# MatrixLantern.net
KiCad netlist of a schematic drawn in Altium Designer
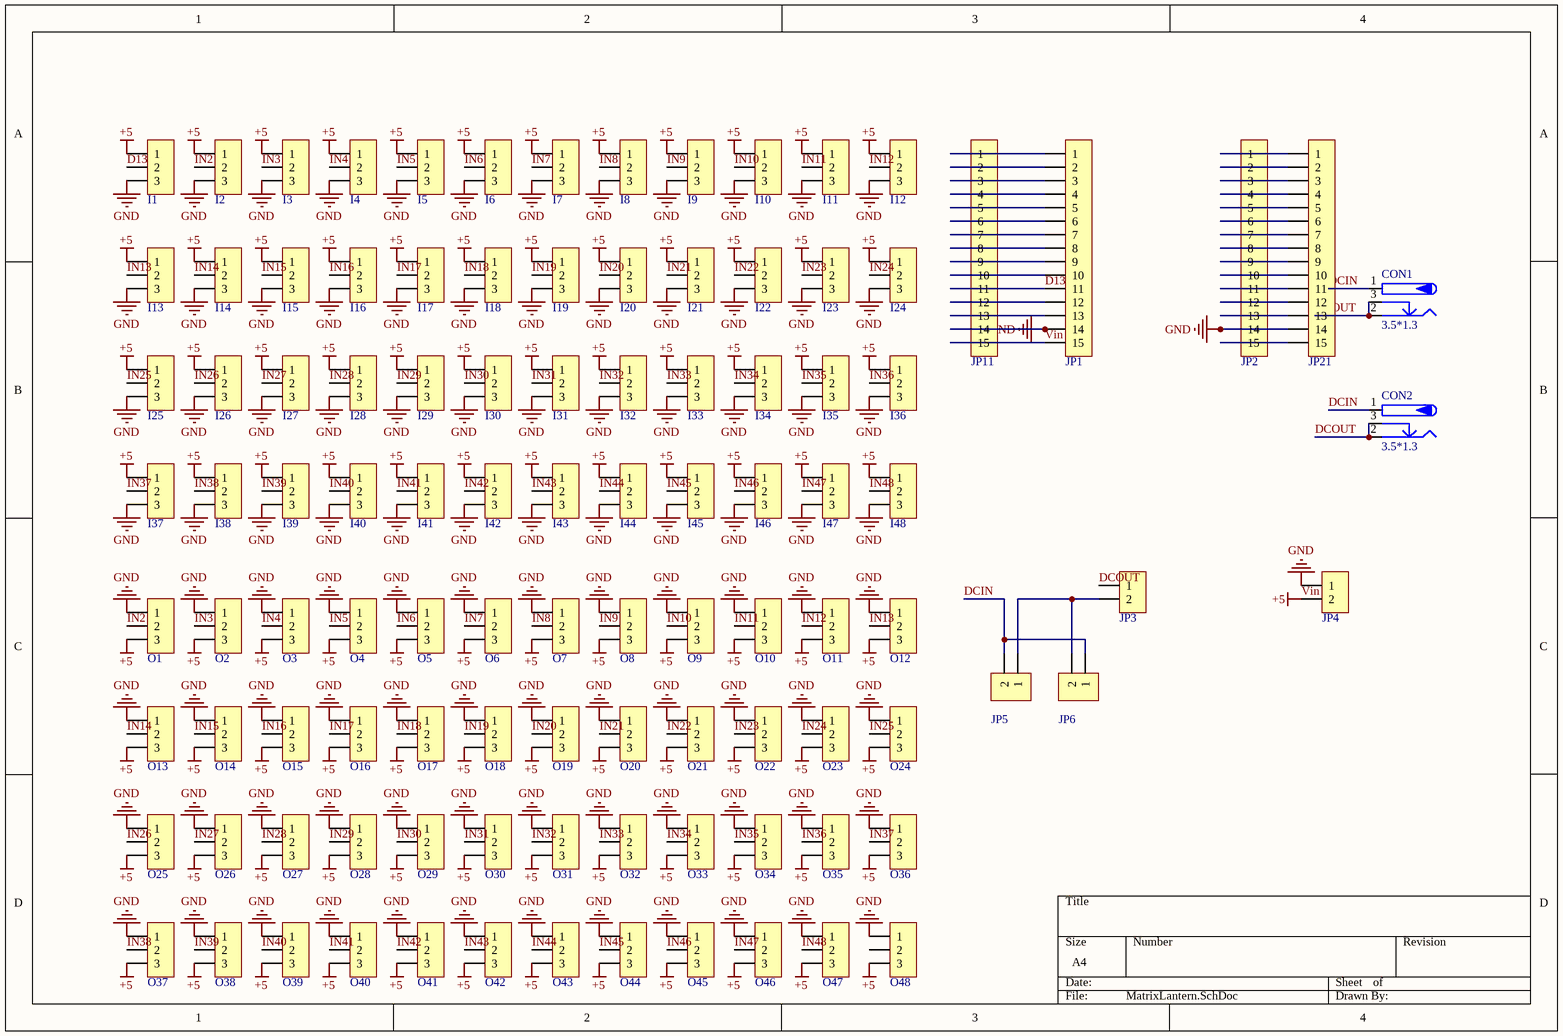
[diagram p0: MatrixLantern.SchDoc]

(export (version "E")
  (design (tool "Eeschema 10.0.6"))
  (components
    (comp (ref "CON1")
      (value "3.5*1.3")
      (footprint "DC-012")
      (description "低压电源接口")
      (fields (field (name "版权归属") "源创客"))
      (libsource (lib "4.1   - 接口类") (part "P-DC"))
    )
    (comp (ref "CON2")
      (value "3.5*1.3")
      (footprint "DC-012")
      (description "低压电源接口")
      (fields (field (name "版权归属") "源创客"))
      (libsource (lib "4.1   - 接口类") (part "P-DC"))
    )
    (comp (ref "I1")
      (value "HDR-1X3")
      (footprint "ZH1.5-WS-3P")
      (description "3P接插件")
      (fields (field (name "版权归属") "源创客"))
      (libsource (lib "4.4   - 接插件-脚距1.5") (part "Header 3"))
    )
    (comp (ref "I2")
      (value "HDR-1X3")
      (footprint "ZH1.5-WS-3P")
      (description "3P接插件")
      (fields (field (name "版权归属") "源创客"))
      (libsource (lib "4.4   - 接插件-脚距1.5") (part "Header 3"))
    )
    (comp (ref "I3")
      (value "HDR-1X3")
      (footprint "ZH1.5-WS-3P")
      (description "3P接插件")
      (fields (field (name "版权归属") "源创客"))
      (libsource (lib "4.4   - 接插件-脚距1.5") (part "Header 3"))
    )
    (comp (ref "I4")
      (value "HDR-1X3")
      (footprint "ZH1.5-WS-3P")
      (description "3P接插件")
      (fields (field (name "版权归属") "源创客"))
      (libsource (lib "4.4   - 接插件-脚距1.5") (part "Header 3"))
    )
    (comp (ref "I5")
      (value "HDR-1X3")
      (footprint "ZH1.5-WS-3P")
      (description "3P接插件")
      (fields (field (name "版权归属") "源创客"))
      (libsource (lib "4.4   - 接插件-脚距1.5") (part "Header 3"))
    )
    (comp (ref "I6")
      (value "HDR-1X3")
      (footprint "ZH1.5-WS-3P")
      (description "3P接插件")
      (fields (field (name "版权归属") "源创客"))
      (libsource (lib "4.4   - 接插件-脚距1.5") (part "Header 3"))
    )
    (comp (ref "I7")
      (value "HDR-1X3")
      (footprint "ZH1.5-WS-3P")
      (description "3P接插件")
      (fields (field (name "版权归属") "源创客"))
      (libsource (lib "4.4   - 接插件-脚距1.5") (part "Header 3"))
    )
    (comp (ref "I8")
      (value "HDR-1X3")
      (footprint "ZH1.5-WS-3P")
      (description "3P接插件")
      (fields (field (name "版权归属") "源创客"))
      (libsource (lib "4.4   - 接插件-脚距1.5") (part "Header 3"))
    )
    (comp (ref "I9")
      (value "HDR-1X3")
      (footprint "ZH1.5-WS-3P")
      (description "3P接插件")
      (fields (field (name "版权归属") "源创客"))
      (libsource (lib "4.4   - 接插件-脚距1.5") (part "Header 3"))
    )
    (comp (ref "I10")
      (value "HDR-1X3")
      (footprint "ZH1.5-WS-3P")
      (description "3P接插件")
      (fields (field (name "版权归属") "源创客"))
      (libsource (lib "4.4   - 接插件-脚距1.5") (part "Header 3"))
    )
    (comp (ref "I11")
      (value "HDR-1X3")
      (footprint "ZH1.5-WS-3P")
      (description "3P接插件")
      (fields (field (name "版权归属") "源创客"))
      (libsource (lib "4.4   - 接插件-脚距1.5") (part "Header 3"))
    )
    (comp (ref "I12")
      (value "HDR-1X3")
      (footprint "ZH1.5-WS-3P")
      (description "3P接插件")
      (fields (field (name "版权归属") "源创客"))
      (libsource (lib "4.4   - 接插件-脚距1.5") (part "Header 3"))
    )
    (comp (ref "I13")
      (value "HDR-1X3")
      (footprint "ZH1.5-WS-3P")
      (description "3P接插件")
      (fields (field (name "版权归属") "源创客"))
      (libsource (lib "4.4   - 接插件-脚距1.5") (part "Header 3"))
    )
    (comp (ref "I14")
      (value "HDR-1X3")
      (footprint "ZH1.5-WS-3P")
      (description "3P接插件")
      (fields (field (name "版权归属") "源创客"))
      (libsource (lib "4.4   - 接插件-脚距1.5") (part "Header 3"))
    )
    (comp (ref "I15")
      (value "HDR-1X3")
      (footprint "ZH1.5-WS-3P")
      (description "3P接插件")
      (fields (field (name "版权归属") "源创客"))
      (libsource (lib "4.4   - 接插件-脚距1.5") (part "Header 3"))
    )
    (comp (ref "I16")
      (value "HDR-1X3")
      (footprint "ZH1.5-WS-3P")
      (description "3P接插件")
      (fields (field (name "版权归属") "源创客"))
      (libsource (lib "4.4   - 接插件-脚距1.5") (part "Header 3"))
    )
    (comp (ref "I17")
      (value "HDR-1X3")
      (footprint "ZH1.5-WS-3P")
      (description "3P接插件")
      (fields (field (name "版权归属") "源创客"))
      (libsource (lib "4.4   - 接插件-脚距1.5") (part "Header 3"))
    )
    (comp (ref "I18")
      (value "HDR-1X3")
      (footprint "ZH1.5-WS-3P")
      (description "3P接插件")
      (fields (field (name "版权归属") "源创客"))
      (libsource (lib "4.4   - 接插件-脚距1.5") (part "Header 3"))
    )
    (comp (ref "I19")
      (value "HDR-1X3")
      (footprint "ZH1.5-WS-3P")
      (description "3P接插件")
      (fields (field (name "版权归属") "源创客"))
      (libsource (lib "4.4   - 接插件-脚距1.5") (part "Header 3"))
    )
    (comp (ref "I20")
      (value "HDR-1X3")
      (footprint "ZH1.5-WS-3P")
      (description "3P接插件")
      (fields (field (name "版权归属") "源创客"))
      (libsource (lib "4.4   - 接插件-脚距1.5") (part "Header 3"))
    )
    (comp (ref "I21")
      (value "HDR-1X3")
      (footprint "ZH1.5-WS-3P")
      (description "3P接插件")
      (fields (field (name "版权归属") "源创客"))
      (libsource (lib "4.4   - 接插件-脚距1.5") (part "Header 3"))
    )
    (comp (ref "I22")
      (value "HDR-1X3")
      (footprint "ZH1.5-WS-3P")
      (description "3P接插件")
      (fields (field (name "版权归属") "源创客"))
      (libsource (lib "4.4   - 接插件-脚距1.5") (part "Header 3"))
    )
    (comp (ref "I23")
      (value "HDR-1X3")
      (footprint "ZH1.5-WS-3P")
      (description "3P接插件")
      (fields (field (name "版权归属") "源创客"))
      (libsource (lib "4.4   - 接插件-脚距1.5") (part "Header 3"))
    )
    (comp (ref "I24")
      (value "HDR-1X3")
      (footprint "ZH1.5-WS-3P")
      (description "3P接插件")
      (fields (field (name "版权归属") "源创客"))
      (libsource (lib "4.4   - 接插件-脚距1.5") (part "Header 3"))
    )
    (comp (ref "I25")
      (value "HDR-1X3")
      (footprint "ZH1.5-WS-3P")
      (description "3P接插件")
      (fields (field (name "版权归属") "源创客"))
      (libsource (lib "4.4   - 接插件-脚距1.5") (part "Header 3"))
    )
    (comp (ref "I26")
      (value "HDR-1X3")
      (footprint "ZH1.5-WS-3P")
      (description "3P接插件")
      (fields (field (name "版权归属") "源创客"))
      (libsource (lib "4.4   - 接插件-脚距1.5") (part "Header 3"))
    )
    (comp (ref "I27")
      (value "HDR-1X3")
      (footprint "ZH1.5-WS-3P")
      (description "3P接插件")
      (fields (field (name "版权归属") "源创客"))
      (libsource (lib "4.4   - 接插件-脚距1.5") (part "Header 3"))
    )
    (comp (ref "I28")
      (value "HDR-1X3")
      (footprint "ZH1.5-WS-3P")
      (description "3P接插件")
      (fields (field (name "版权归属") "源创客"))
      (libsource (lib "4.4   - 接插件-脚距1.5") (part "Header 3"))
    )
    (comp (ref "I29")
      (value "HDR-1X3")
      (footprint "ZH1.5-WS-3P")
      (description "3P接插件")
      (fields (field (name "版权归属") "源创客"))
      (libsource (lib "4.4   - 接插件-脚距1.5") (part "Header 3"))
    )
    (comp (ref "I30")
      (value "HDR-1X3")
      (footprint "ZH1.5-WS-3P")
      (description "3P接插件")
      (fields (field (name "版权归属") "源创客"))
      (libsource (lib "4.4   - 接插件-脚距1.5") (part "Header 3"))
    )
    (comp (ref "I31")
      (value "HDR-1X3")
      (footprint "ZH1.5-WS-3P")
      (description "3P接插件")
      (fields (field (name "版权归属") "源创客"))
      (libsource (lib "4.4   - 接插件-脚距1.5") (part "Header 3"))
    )
    (comp (ref "I32")
      (value "HDR-1X3")
      (footprint "ZH1.5-WS-3P")
      (description "3P接插件")
      (fields (field (name "版权归属") "源创客"))
      (libsource (lib "4.4   - 接插件-脚距1.5") (part "Header 3"))
    )
    (comp (ref "I33")
      (value "HDR-1X3")
      (footprint "ZH1.5-WS-3P")
      (description "3P接插件")
      (fields (field (name "版权归属") "源创客"))
      (libsource (lib "4.4   - 接插件-脚距1.5") (part "Header 3"))
    )
    (comp (ref "I34")
      (value "HDR-1X3")
      (footprint "ZH1.5-WS-3P")
      (description "3P接插件")
      (fields (field (name "版权归属") "源创客"))
      (libsource (lib "4.4   - 接插件-脚距1.5") (part "Header 3"))
    )
    (comp (ref "I35")
      (value "HDR-1X3")
      (footprint "ZH1.5-WS-3P")
      (description "3P接插件")
      (fields (field (name "版权归属") "源创客"))
      (libsource (lib "4.4   - 接插件-脚距1.5") (part "Header 3"))
    )
    (comp (ref "I36")
      (value "HDR-1X3")
      (footprint "ZH1.5-WS-3P")
      (description "3P接插件")
      (fields (field (name "版权归属") "源创客"))
      (libsource (lib "4.4   - 接插件-脚距1.5") (part "Header 3"))
    )
    (comp (ref "I37")
      (value "HDR-1X3")
      (footprint "ZH1.5-WS-3P")
      (description "3P接插件")
      (fields (field (name "版权归属") "源创客"))
      (libsource (lib "4.4   - 接插件-脚距1.5") (part "Header 3"))
    )
    (comp (ref "I38")
      (value "HDR-1X3")
      (footprint "ZH1.5-WS-3P")
      (description "3P接插件")
      (fields (field (name "版权归属") "源创客"))
      (libsource (lib "4.4   - 接插件-脚距1.5") (part "Header 3"))
    )
    (comp (ref "I39")
      (value "HDR-1X3")
      (footprint "ZH1.5-WS-3P")
      (description "3P接插件")
      (fields (field (name "版权归属") "源创客"))
      (libsource (lib "4.4   - 接插件-脚距1.5") (part "Header 3"))
    )
    (comp (ref "I40")
      (value "HDR-1X3")
      (footprint "ZH1.5-WS-3P")
      (description "3P接插件")
      (fields (field (name "版权归属") "源创客"))
      (libsource (lib "4.4   - 接插件-脚距1.5") (part "Header 3"))
    )
    (comp (ref "I41")
      (value "HDR-1X3")
      (footprint "ZH1.5-WS-3P")
      (description "3P接插件")
      (fields (field (name "版权归属") "源创客"))
      (libsource (lib "4.4   - 接插件-脚距1.5") (part "Header 3"))
    )
    (comp (ref "I42")
      (value "HDR-1X3")
      (footprint "ZH1.5-WS-3P")
      (description "3P接插件")
      (fields (field (name "版权归属") "源创客"))
      (libsource (lib "4.4   - 接插件-脚距1.5") (part "Header 3"))
    )
    (comp (ref "I43")
      (value "HDR-1X3")
      (footprint "ZH1.5-WS-3P")
      (description "3P接插件")
      (fields (field (name "版权归属") "源创客"))
      (libsource (lib "4.4   - 接插件-脚距1.5") (part "Header 3"))
    )
    (comp (ref "I44")
      (value "HDR-1X3")
      (footprint "ZH1.5-WS-3P")
      (description "3P接插件")
      (fields (field (name "版权归属") "源创客"))
      (libsource (lib "4.4   - 接插件-脚距1.5") (part "Header 3"))
    )
    (comp (ref "I45")
      (value "HDR-1X3")
      (footprint "ZH1.5-WS-3P")
      (description "3P接插件")
      (fields (field (name "版权归属") "源创客"))
      (libsource (lib "4.4   - 接插件-脚距1.5") (part "Header 3"))
    )
    (comp (ref "I46")
      (value "HDR-1X3")
      (footprint "ZH1.5-WS-3P")
      (description "3P接插件")
      (fields (field (name "版权归属") "源创客"))
      (libsource (lib "4.4   - 接插件-脚距1.5") (part "Header 3"))
    )
    (comp (ref "I47")
      (value "HDR-1X3")
      (footprint "ZH1.5-WS-3P")
      (description "3P接插件")
      (fields (field (name "版权归属") "源创客"))
      (libsource (lib "4.4   - 接插件-脚距1.5") (part "Header 3"))
    )
    (comp (ref "I48")
      (value "HDR-1X3")
      (footprint "ZH1.5-WS-3P")
      (description "3P接插件")
      (fields (field (name "版权归属") "源创客"))
      (libsource (lib "4.4   - 接插件-脚距1.5") (part "Header 3"))
    )
    (comp (ref "JP1")
      (value "HDR-1X15")
      (footprint "HDR2.54-M-LI-15P")
      (description "15P接插件")
      (fields (field (name "版权归属") "源创客"))
      (libsource (lib "4.6   - 接插件-脚距2.54") (part "Header 15"))
    )
    (comp (ref "JP2")
      (value "HDR-1X15")
      (footprint "HDR2.54-M-LI-15P")
      (description "15P接插件")
      (fields (field (name "版权归属") "源创客"))
      (libsource (lib "4.6   - 接插件-脚距2.54") (part "Header 15"))
    )
    (comp (ref "JP3")
      (value "HDR-1X2")
      (footprint "KF350-2P")
      (description "2P接插件")
      (fields (field (name "版权归属") "源创客"))
      (libsource (lib "") (part "Header 2_1"))
    )
    (comp (ref "JP4")
      (value "HDR-1X2")
      (footprint "KF350-2P")
      (description "2P接插件")
      (fields (field (name "版权归属") "源创客"))
      (libsource (lib "") (part "Header 2_1"))
    )
    (comp (ref "JP5")
      (value "HDR-1X2")
      (footprint "KF350-2P")
      (description "2P接插件")
      (fields (field (name "版权归属") "源创客"))
      (libsource (lib "4.7   - 接插件-脚距3.5") (part "Header 2"))
    )
    (comp (ref "JP6")
      (value "HDR-1X2")
      (footprint "KF350-2P")
      (description "2P接插件")
      (fields (field (name "版权归属") "源创客"))
      (libsource (lib "4.7   - 接插件-脚距3.5") (part "Header 2"))
    )
    (comp (ref "JP11")
      (value "HDR-1X15")
      (footprint "HDR2.54-LI-15P")
      (description "15P接插件")
      (fields (field (name "版权归属") "源创客"))
      (libsource (lib "4.6   - 接插件-脚距2.54") (part "Header 15"))
    )
    (comp (ref "JP21")
      (value "HDR-1X15")
      (footprint "HDR2.54-LI-15P")
      (description "15P接插件")
      (fields (field (name "版权归属") "源创客"))
      (libsource (lib "4.6   - 接插件-脚距2.54") (part "Header 15"))
    )
    (comp (ref "O1")
      (value "HDR-1X3")
      (footprint "ZH1.5-WS-3P")
      (description "3P接插件")
      (fields (field (name "版权归属") "源创客"))
      (libsource (lib "4.4   - 接插件-脚距1.5") (part "Header 3"))
    )
    (comp (ref "O2")
      (value "HDR-1X3")
      (footprint "ZH1.5-WS-3P")
      (description "3P接插件")
      (fields (field (name "版权归属") "源创客"))
      (libsource (lib "4.4   - 接插件-脚距1.5") (part "Header 3"))
    )
    (comp (ref "O3")
      (value "HDR-1X3")
      (footprint "ZH1.5-WS-3P")
      (description "3P接插件")
      (fields (field (name "版权归属") "源创客"))
      (libsource (lib "4.4   - 接插件-脚距1.5") (part "Header 3"))
    )
    (comp (ref "O4")
      (value "HDR-1X3")
      (footprint "ZH1.5-WS-3P")
      (description "3P接插件")
      (fields (field (name "版权归属") "源创客"))
      (libsource (lib "4.4   - 接插件-脚距1.5") (part "Header 3"))
    )
    (comp (ref "O5")
      (value "HDR-1X3")
      (footprint "ZH1.5-WS-3P")
      (description "3P接插件")
      (fields (field (name "版权归属") "源创客"))
      (libsource (lib "4.4   - 接插件-脚距1.5") (part "Header 3"))
    )
    (comp (ref "O6")
      (value "HDR-1X3")
      (footprint "ZH1.5-WS-3P")
      (description "3P接插件")
      (fields (field (name "版权归属") "源创客"))
      (libsource (lib "4.4   - 接插件-脚距1.5") (part "Header 3"))
    )
    (comp (ref "O7")
      (value "HDR-1X3")
      (footprint "ZH1.5-WS-3P")
      (description "3P接插件")
      (fields (field (name "版权归属") "源创客"))
      (libsource (lib "4.4   - 接插件-脚距1.5") (part "Header 3"))
    )
    (comp (ref "O8")
      (value "HDR-1X3")
      (footprint "ZH1.5-WS-3P")
      (description "3P接插件")
      (fields (field (name "版权归属") "源创客"))
      (libsource (lib "4.4   - 接插件-脚距1.5") (part "Header 3"))
    )
    (comp (ref "O9")
      (value "HDR-1X3")
      (footprint "ZH1.5-WS-3P")
      (description "3P接插件")
      (fields (field (name "版权归属") "源创客"))
      (libsource (lib "4.4   - 接插件-脚距1.5") (part "Header 3"))
    )
    (comp (ref "O10")
      (value "HDR-1X3")
      (footprint "ZH1.5-WS-3P")
      (description "3P接插件")
      (fields (field (name "版权归属") "源创客"))
      (libsource (lib "4.4   - 接插件-脚距1.5") (part "Header 3"))
    )
    (comp (ref "O11")
      (value "HDR-1X3")
      (footprint "ZH1.5-WS-3P")
      (description "3P接插件")
      (fields (field (name "版权归属") "源创客"))
      (libsource (lib "4.4   - 接插件-脚距1.5") (part "Header 3"))
    )
    (comp (ref "O12")
      (value "HDR-1X3")
      (footprint "ZH1.5-WS-3P")
      (description "3P接插件")
      (fields (field (name "版权归属") "源创客"))
      (libsource (lib "4.4   - 接插件-脚距1.5") (part "Header 3"))
    )
    (comp (ref "O13")
      (value "HDR-1X3")
      (footprint "ZH1.5-WS-3P")
      (description "3P接插件")
      (fields (field (name "版权归属") "源创客"))
      (libsource (lib "4.4   - 接插件-脚距1.5") (part "Header 3"))
    )
    (comp (ref "O14")
      (value "HDR-1X3")
      (footprint "ZH1.5-WS-3P")
      (description "3P接插件")
      (fields (field (name "版权归属") "源创客"))
      (libsource (lib "4.4   - 接插件-脚距1.5") (part "Header 3"))
    )
    (comp (ref "O15")
      (value "HDR-1X3")
      (footprint "ZH1.5-WS-3P")
      (description "3P接插件")
      (fields (field (name "版权归属") "源创客"))
      (libsource (lib "4.4   - 接插件-脚距1.5") (part "Header 3"))
    )
    (comp (ref "O16")
      (value "HDR-1X3")
      (footprint "ZH1.5-WS-3P")
      (description "3P接插件")
      (fields (field (name "版权归属") "源创客"))
      (libsource (lib "4.4   - 接插件-脚距1.5") (part "Header 3"))
    )
    (comp (ref "O17")
      (value "HDR-1X3")
      (footprint "ZH1.5-WS-3P")
      (description "3P接插件")
      (fields (field (name "版权归属") "源创客"))
      (libsource (lib "4.4   - 接插件-脚距1.5") (part "Header 3"))
    )
    (comp (ref "O18")
      (value "HDR-1X3")
      (footprint "ZH1.5-WS-3P")
      (description "3P接插件")
      (fields (field (name "版权归属") "源创客"))
      (libsource (lib "4.4   - 接插件-脚距1.5") (part "Header 3"))
    )
    (comp (ref "O19")
      (value "HDR-1X3")
      (footprint "ZH1.5-WS-3P")
      (description "3P接插件")
      (fields (field (name "版权归属") "源创客"))
      (libsource (lib "4.4   - 接插件-脚距1.5") (part "Header 3"))
    )
    (comp (ref "O20")
      (value "HDR-1X3")
      (footprint "ZH1.5-WS-3P")
      (description "3P接插件")
      (fields (field (name "版权归属") "源创客"))
      (libsource (lib "4.4   - 接插件-脚距1.5") (part "Header 3"))
    )
    (comp (ref "O21")
      (value "HDR-1X3")
      (footprint "ZH1.5-WS-3P")
      (description "3P接插件")
      (fields (field (name "版权归属") "源创客"))
      (libsource (lib "4.4   - 接插件-脚距1.5") (part "Header 3"))
    )
    (comp (ref "O22")
      (value "HDR-1X3")
      (footprint "ZH1.5-WS-3P")
      (description "3P接插件")
      (fields (field (name "版权归属") "源创客"))
      (libsource (lib "4.4   - 接插件-脚距1.5") (part "Header 3"))
    )
    (comp (ref "O23")
      (value "HDR-1X3")
      (footprint "ZH1.5-WS-3P")
      (description "3P接插件")
      (fields (field (name "版权归属") "源创客"))
      (libsource (lib "4.4   - 接插件-脚距1.5") (part "Header 3"))
    )
    (comp (ref "O24")
      (value "HDR-1X3")
      (footprint "ZH1.5-WS-3P")
      (description "3P接插件")
      (fields (field (name "版权归属") "源创客"))
      (libsource (lib "4.4   - 接插件-脚距1.5") (part "Header 3"))
    )
    (comp (ref "O25")
      (value "HDR-1X3")
      (footprint "ZH1.5-WS-3P")
      (description "3P接插件")
      (fields (field (name "版权归属") "源创客"))
      (libsource (lib "4.4   - 接插件-脚距1.5") (part "Header 3"))
    )
    (comp (ref "O26")
      (value "HDR-1X3")
      (footprint "ZH1.5-WS-3P")
      (description "3P接插件")
      (fields (field (name "版权归属") "源创客"))
      (libsource (lib "4.4   - 接插件-脚距1.5") (part "Header 3"))
    )
    (comp (ref "O27")
      (value "HDR-1X3")
      (footprint "ZH1.5-WS-3P")
      (description "3P接插件")
      (fields (field (name "版权归属") "源创客"))
      (libsource (lib "4.4   - 接插件-脚距1.5") (part "Header 3"))
    )
    (comp (ref "O28")
      (value "HDR-1X3")
      (footprint "ZH1.5-WS-3P")
      (description "3P接插件")
      (fields (field (name "版权归属") "源创客"))
      (libsource (lib "4.4   - 接插件-脚距1.5") (part "Header 3"))
    )
    (comp (ref "O29")
      (value "HDR-1X3")
      (footprint "ZH1.5-WS-3P")
      (description "3P接插件")
      (fields (field (name "版权归属") "源创客"))
      (libsource (lib "4.4   - 接插件-脚距1.5") (part "Header 3"))
    )
    (comp (ref "O30")
      (value "HDR-1X3")
      (footprint "ZH1.5-WS-3P")
      (description "3P接插件")
      (fields (field (name "版权归属") "源创客"))
      (libsource (lib "4.4   - 接插件-脚距1.5") (part "Header 3"))
    )
    (comp (ref "O31")
      (value "HDR-1X3")
      (footprint "ZH1.5-WS-3P")
      (description "3P接插件")
      (fields (field (name "版权归属") "源创客"))
      (libsource (lib "4.4   - 接插件-脚距1.5") (part "Header 3"))
    )
    (comp (ref "O32")
      (value "HDR-1X3")
      (footprint "ZH1.5-WS-3P")
      (description "3P接插件")
      (fields (field (name "版权归属") "源创客"))
      (libsource (lib "4.4   - 接插件-脚距1.5") (part "Header 3"))
    )
    (comp (ref "O33")
      (value "HDR-1X3")
      (footprint "ZH1.5-WS-3P")
      (description "3P接插件")
      (fields (field (name "版权归属") "源创客"))
      (libsource (lib "4.4   - 接插件-脚距1.5") (part "Header 3"))
    )
    (comp (ref "O34")
      (value "HDR-1X3")
      (footprint "ZH1.5-WS-3P")
      (description "3P接插件")
      (fields (field (name "版权归属") "源创客"))
      (libsource (lib "4.4   - 接插件-脚距1.5") (part "Header 3"))
    )
    (comp (ref "O35")
      (value "HDR-1X3")
      (footprint "ZH1.5-WS-3P")
      (description "3P接插件")
      (fields (field (name "版权归属") "源创客"))
      (libsource (lib "4.4   - 接插件-脚距1.5") (part "Header 3"))
    )
    (comp (ref "O36")
      (value "HDR-1X3")
      (footprint "ZH1.5-WS-3P")
      (description "3P接插件")
      (fields (field (name "版权归属") "源创客"))
      (libsource (lib "4.4   - 接插件-脚距1.5") (part "Header 3"))
    )
    (comp (ref "O37")
      (value "HDR-1X3")
      (footprint "ZH1.5-WS-3P")
      (description "3P接插件")
      (fields (field (name "版权归属") "源创客"))
      (libsource (lib "4.4   - 接插件-脚距1.5") (part "Header 3"))
    )
    (comp (ref "O38")
      (value "HDR-1X3")
      (footprint "ZH1.5-WS-3P")
      (description "3P接插件")
      (fields (field (name "版权归属") "源创客"))
      (libsource (lib "4.4   - 接插件-脚距1.5") (part "Header 3"))
    )
    (comp (ref "O39")
      (value "HDR-1X3")
      (footprint "ZH1.5-WS-3P")
      (description "3P接插件")
      (fields (field (name "版权归属") "源创客"))
      (libsource (lib "4.4   - 接插件-脚距1.5") (part "Header 3"))
    )
    (comp (ref "O40")
      (value "HDR-1X3")
      (footprint "ZH1.5-WS-3P")
      (description "3P接插件")
      (fields (field (name "版权归属") "源创客"))
      (libsource (lib "4.4   - 接插件-脚距1.5") (part "Header 3"))
    )
    (comp (ref "O41")
      (value "HDR-1X3")
      (footprint "ZH1.5-WS-3P")
      (description "3P接插件")
      (fields (field (name "版权归属") "源创客"))
      (libsource (lib "4.4   - 接插件-脚距1.5") (part "Header 3"))
    )
    (comp (ref "O42")
      (value "HDR-1X3")
      (footprint "ZH1.5-WS-3P")
      (description "3P接插件")
      (fields (field (name "版权归属") "源创客"))
      (libsource (lib "4.4   - 接插件-脚距1.5") (part "Header 3"))
    )
    (comp (ref "O43")
      (value "HDR-1X3")
      (footprint "ZH1.5-WS-3P")
      (description "3P接插件")
      (fields (field (name "版权归属") "源创客"))
      (libsource (lib "4.4   - 接插件-脚距1.5") (part "Header 3"))
    )
    (comp (ref "O44")
      (value "HDR-1X3")
      (footprint "ZH1.5-WS-3P")
      (description "3P接插件")
      (fields (field (name "版权归属") "源创客"))
      (libsource (lib "4.4   - 接插件-脚距1.5") (part "Header 3"))
    )
    (comp (ref "O45")
      (value "HDR-1X3")
      (footprint "ZH1.5-WS-3P")
      (description "3P接插件")
      (fields (field (name "版权归属") "源创客"))
      (libsource (lib "4.4   - 接插件-脚距1.5") (part "Header 3"))
    )
    (comp (ref "O46")
      (value "HDR-1X3")
      (footprint "ZH1.5-WS-3P")
      (description "3P接插件")
      (fields (field (name "版权归属") "源创客"))
      (libsource (lib "4.4   - 接插件-脚距1.5") (part "Header 3"))
    )
    (comp (ref "O47")
      (value "HDR-1X3")
      (footprint "ZH1.5-WS-3P")
      (description "3P接插件")
      (fields (field (name "版权归属") "源创客"))
      (libsource (lib "4.4   - 接插件-脚距1.5") (part "Header 3"))
    )
    (comp (ref "O48")
      (value "HDR-1X3")
      (footprint "ZH1.5-WS-3P")
      (description "3P接插件")
      (fields (field (name "版权归属") "源创客"))
      (libsource (lib "4.4   - 接插件-脚距1.5") (part "Header 3"))
    )
  )
  (nets
    (net (code "1") (name "+5") (class "Default")
      (node (ref "I1") (pin "1") (pinfunction "1_1") (pintype "passive"))
      (node (ref "I10") (pin "1") (pinfunction "1_1") (pintype "passive"))
      (node (ref "I11") (pin "1") (pinfunction "1_1") (pintype "passive"))
      (node (ref "I12") (pin "1") (pinfunction "1_1") (pintype "passive"))
      (node (ref "I13") (pin "1") (pinfunction "1_1") (pintype "passive"))
      (node (ref "I14") (pin "1") (pinfunction "1_1") (pintype "passive"))
      (node (ref "I15") (pin "1") (pinfunction "1_1") (pintype "passive"))
      (node (ref "I16") (pin "1") (pinfunction "1_1") (pintype "passive"))
      (node (ref "I17") (pin "1") (pinfunction "1_1") (pintype "passive"))
      (node (ref "I18") (pin "1") (pinfunction "1_1") (pintype "passive"))
      (node (ref "I19") (pin "1") (pinfunction "1_1") (pintype "passive"))
      (node (ref "I2") (pin "1") (pinfunction "1_1") (pintype "passive"))
      (node (ref "I20") (pin "1") (pinfunction "1_1") (pintype "passive"))
      (node (ref "I21") (pin "1") (pinfunction "1_1") (pintype "passive"))
      (node (ref "I22") (pin "1") (pinfunction "1_1") (pintype "passive"))
      (node (ref "I23") (pin "1") (pinfunction "1_1") (pintype "passive"))
      (node (ref "I24") (pin "1") (pinfunction "1_1") (pintype "passive"))
      (node (ref "I25") (pin "1") (pinfunction "1_1") (pintype "passive"))
      (node (ref "I26") (pin "1") (pinfunction "1_1") (pintype "passive"))
      (node (ref "I27") (pin "1") (pinfunction "1_1") (pintype "passive"))
      (node (ref "I28") (pin "1") (pinfunction "1_1") (pintype "passive"))
      (node (ref "I29") (pin "1") (pinfunction "1_1") (pintype "passive"))
      (node (ref "I3") (pin "1") (pinfunction "1_1") (pintype "passive"))
      (node (ref "I30") (pin "1") (pinfunction "1_1") (pintype "passive"))
      (node (ref "I31") (pin "1") (pinfunction "1_1") (pintype "passive"))
      (node (ref "I32") (pin "1") (pinfunction "1_1") (pintype "passive"))
      (node (ref "I33") (pin "1") (pinfunction "1_1") (pintype "passive"))
      (node (ref "I34") (pin "1") (pinfunction "1_1") (pintype "passive"))
      (node (ref "I35") (pin "1") (pinfunction "1_1") (pintype "passive"))
      (node (ref "I36") (pin "1") (pinfunction "1_1") (pintype "passive"))
      (node (ref "I37") (pin "1") (pinfunction "1_1") (pintype "passive"))
      (node (ref "I38") (pin "1") (pinfunction "1_1") (pintype "passive"))
      (node (ref "I39") (pin "1") (pinfunction "1_1") (pintype "passive"))
      (node (ref "I4") (pin "1") (pinfunction "1_1") (pintype "passive"))
      (node (ref "I40") (pin "1") (pinfunction "1_1") (pintype "passive"))
      (node (ref "I41") (pin "1") (pinfunction "1_1") (pintype "passive"))
      (node (ref "I42") (pin "1") (pinfunction "1_1") (pintype "passive"))
      (node (ref "I43") (pin "1") (pinfunction "1_1") (pintype "passive"))
      (node (ref "I44") (pin "1") (pinfunction "1_1") (pintype "passive"))
      (node (ref "I45") (pin "1") (pinfunction "1_1") (pintype "passive"))
      (node (ref "I46") (pin "1") (pinfunction "1_1") (pintype "passive"))
      (node (ref "I47") (pin "1") (pinfunction "1_1") (pintype "passive"))
      (node (ref "I48") (pin "1") (pinfunction "1_1") (pintype "passive"))
      (node (ref "I5") (pin "1") (pinfunction "1_1") (pintype "passive"))
      (node (ref "I6") (pin "1") (pinfunction "1_1") (pintype "passive"))
      (node (ref "I7") (pin "1") (pinfunction "1_1") (pintype "passive"))
      (node (ref "I8") (pin "1") (pinfunction "1_1") (pintype "passive"))
      (node (ref "I9") (pin "1") (pinfunction "1_1") (pintype "passive"))
      (node (ref "JP1") (pin "15") (pinfunction "15_15") (pintype "passive"))
      (node (ref "JP11") (pin "15") (pinfunction "15_15") (pintype "passive"))
      (node (ref "JP4") (pin "2") (pinfunction "2_2") (pintype "passive"))
      (node (ref "O1") (pin "3") (pinfunction "3_3") (pintype "passive"))
      (node (ref "O10") (pin "3") (pinfunction "3_3") (pintype "passive"))
      (node (ref "O11") (pin "3") (pinfunction "3_3") (pintype "passive"))
      (node (ref "O12") (pin "3") (pinfunction "3_3") (pintype "passive"))
      (node (ref "O13") (pin "3") (pinfunction "3_3") (pintype "passive"))
      (node (ref "O14") (pin "3") (pinfunction "3_3") (pintype "passive"))
      (node (ref "O15") (pin "3") (pinfunction "3_3") (pintype "passive"))
      (node (ref "O16") (pin "3") (pinfunction "3_3") (pintype "passive"))
      (node (ref "O17") (pin "3") (pinfunction "3_3") (pintype "passive"))
      (node (ref "O18") (pin "3") (pinfunction "3_3") (pintype "passive"))
      (node (ref "O19") (pin "3") (pinfunction "3_3") (pintype "passive"))
      (node (ref "O2") (pin "3") (pinfunction "3_3") (pintype "passive"))
      (node (ref "O20") (pin "3") (pinfunction "3_3") (pintype "passive"))
      (node (ref "O21") (pin "3") (pinfunction "3_3") (pintype "passive"))
      (node (ref "O22") (pin "3") (pinfunction "3_3") (pintype "passive"))
      (node (ref "O23") (pin "3") (pinfunction "3_3") (pintype "passive"))
      (node (ref "O24") (pin "3") (pinfunction "3_3") (pintype "passive"))
      (node (ref "O25") (pin "3") (pinfunction "3_3") (pintype "passive"))
      (node (ref "O26") (pin "3") (pinfunction "3_3") (pintype "passive"))
      (node (ref "O27") (pin "3") (pinfunction "3_3") (pintype "passive"))
      (node (ref "O28") (pin "3") (pinfunction "3_3") (pintype "passive"))
      (node (ref "O29") (pin "3") (pinfunction "3_3") (pintype "passive"))
      (node (ref "O3") (pin "3") (pinfunction "3_3") (pintype "passive"))
      (node (ref "O30") (pin "3") (pinfunction "3_3") (pintype "passive"))
      (node (ref "O31") (pin "3") (pinfunction "3_3") (pintype "passive"))
      (node (ref "O32") (pin "3") (pinfunction "3_3") (pintype "passive"))
      (node (ref "O33") (pin "3") (pinfunction "3_3") (pintype "passive"))
      (node (ref "O34") (pin "3") (pinfunction "3_3") (pintype "passive"))
      (node (ref "O35") (pin "3") (pinfunction "3_3") (pintype "passive"))
      (node (ref "O36") (pin "3") (pinfunction "3_3") (pintype "passive"))
      (node (ref "O37") (pin "3") (pinfunction "3_3") (pintype "passive"))
      (node (ref "O38") (pin "3") (pinfunction "3_3") (pintype "passive"))
      (node (ref "O39") (pin "3") (pinfunction "3_3") (pintype "passive"))
      (node (ref "O4") (pin "3") (pinfunction "3_3") (pintype "passive"))
      (node (ref "O40") (pin "3") (pinfunction "3_3") (pintype "passive"))
      (node (ref "O41") (pin "3") (pinfunction "3_3") (pintype "passive"))
      (node (ref "O42") (pin "3") (pinfunction "3_3") (pintype "passive"))
      (node (ref "O43") (pin "3") (pinfunction "3_3") (pintype "passive"))
      (node (ref "O44") (pin "3") (pinfunction "3_3") (pintype "passive"))
      (node (ref "O45") (pin "3") (pinfunction "3_3") (pintype "passive"))
      (node (ref "O46") (pin "3") (pinfunction "3_3") (pintype "passive"))
      (node (ref "O47") (pin "3") (pinfunction "3_3") (pintype "passive"))
      (node (ref "O48") (pin "3") (pinfunction "3_3") (pintype "passive"))
      (node (ref "O5") (pin "3") (pinfunction "3_3") (pintype "passive"))
      (node (ref "O6") (pin "3") (pinfunction "3_3") (pintype "passive"))
      (node (ref "O7") (pin "3") (pinfunction "3_3") (pintype "passive"))
      (node (ref "O8") (pin "3") (pinfunction "3_3") (pintype "passive"))
      (node (ref "O9") (pin "3") (pinfunction "3_3") (pintype "passive"))
    )
    (net (code "2") (name "/D13") (class "Default")
      (node (ref "I1") (pin "2") (pinfunction "2_2") (pintype "passive"))
      (node (ref "JP1") (pin "11") (pinfunction "11_11") (pintype "passive"))
      (node (ref "JP11") (pin "11") (pinfunction "11_11") (pintype "passive"))
    )
    (net (code "3") (name "/DCIN") (class "Default")
      (node (ref "CON1") (pin "1") (pintype "power_in"))
      (node (ref "CON2") (pin "1") (pintype "power_in"))
      (node (ref "JP5") (pin "2") (pinfunction "2_2") (pintype "passive"))
      (node (ref "JP6") (pin "1") (pinfunction "1_1") (pintype "passive"))
    )
    (net (code "4") (name "/DCOUT") (class "Default")
      (node (ref "CON1") (pin "2") (pintype "power_in"))
      (node (ref "CON1") (pin "3") (pintype "power_in"))
      (node (ref "CON2") (pin "2") (pintype "power_in"))
      (node (ref "CON2") (pin "3") (pintype "power_in"))
      (node (ref "JP3") (pin "1") (pinfunction "1_1") (pintype "passive"))
    )
    (net (code "5") (name "/IN2") (class "Default")
      (node (ref "I2") (pin "2") (pinfunction "2_2") (pintype "passive"))
      (node (ref "O1") (pin "2") (pinfunction "2_2") (pintype "passive"))
    )
    (net (code "6") (name "/IN3") (class "Default")
      (node (ref "I3") (pin "2") (pinfunction "2_2") (pintype "passive"))
      (node (ref "O2") (pin "2") (pinfunction "2_2") (pintype "passive"))
    )
    (net (code "7") (name "/IN4") (class "Default")
      (node (ref "I4") (pin "2") (pinfunction "2_2") (pintype "passive"))
      (node (ref "O3") (pin "2") (pinfunction "2_2") (pintype "passive"))
    )
    (net (code "8") (name "/IN5") (class "Default")
      (node (ref "I5") (pin "2") (pinfunction "2_2") (pintype "passive"))
      (node (ref "O4") (pin "2") (pinfunction "2_2") (pintype "passive"))
    )
    (net (code "9") (name "/IN6") (class "Default")
      (node (ref "I6") (pin "2") (pinfunction "2_2") (pintype "passive"))
      (node (ref "O5") (pin "2") (pinfunction "2_2") (pintype "passive"))
    )
    (net (code "10") (name "/IN7") (class "Default")
      (node (ref "I7") (pin "2") (pinfunction "2_2") (pintype "passive"))
      (node (ref "O6") (pin "2") (pinfunction "2_2") (pintype "passive"))
    )
    (net (code "11") (name "/IN8") (class "Default")
      (node (ref "I8") (pin "2") (pinfunction "2_2") (pintype "passive"))
      (node (ref "O7") (pin "2") (pinfunction "2_2") (pintype "passive"))
    )
    (net (code "12") (name "/IN9") (class "Default")
      (node (ref "I9") (pin "2") (pinfunction "2_2") (pintype "passive"))
      (node (ref "O8") (pin "2") (pinfunction "2_2") (pintype "passive"))
    )
    (net (code "13") (name "/IN10") (class "Default")
      (node (ref "I10") (pin "2") (pinfunction "2_2") (pintype "passive"))
      (node (ref "O9") (pin "2") (pinfunction "2_2") (pintype "passive"))
    )
    (net (code "14") (name "/IN11") (class "Default")
      (node (ref "I11") (pin "2") (pinfunction "2_2") (pintype "passive"))
      (node (ref "O10") (pin "2") (pinfunction "2_2") (pintype "passive"))
    )
    (net (code "15") (name "/IN12") (class "Default")
      (node (ref "I12") (pin "2") (pinfunction "2_2") (pintype "passive"))
      (node (ref "O11") (pin "2") (pinfunction "2_2") (pintype "passive"))
    )
    (net (code "16") (name "/IN13") (class "Default")
      (node (ref "I13") (pin "2") (pinfunction "2_2") (pintype "passive"))
      (node (ref "O12") (pin "2") (pinfunction "2_2") (pintype "passive"))
    )
    (net (code "17") (name "/IN14") (class "Default")
      (node (ref "I14") (pin "2") (pinfunction "2_2") (pintype "passive"))
      (node (ref "O13") (pin "2") (pinfunction "2_2") (pintype "passive"))
    )
    (net (code "18") (name "/IN15") (class "Default")
      (node (ref "I15") (pin "2") (pinfunction "2_2") (pintype "passive"))
      (node (ref "O14") (pin "2") (pinfunction "2_2") (pintype "passive"))
    )
    (net (code "19") (name "/IN16") (class "Default")
      (node (ref "I16") (pin "2") (pinfunction "2_2") (pintype "passive"))
      (node (ref "O15") (pin "2") (pinfunction "2_2") (pintype "passive"))
    )
    (net (code "20") (name "/IN17") (class "Default")
      (node (ref "I17") (pin "2") (pinfunction "2_2") (pintype "passive"))
      (node (ref "O16") (pin "2") (pinfunction "2_2") (pintype "passive"))
    )
    (net (code "21") (name "/IN18") (class "Default")
      (node (ref "I18") (pin "2") (pinfunction "2_2") (pintype "passive"))
      (node (ref "O17") (pin "2") (pinfunction "2_2") (pintype "passive"))
    )
    (net (code "22") (name "/IN19") (class "Default")
      (node (ref "I19") (pin "2") (pinfunction "2_2") (pintype "passive"))
      (node (ref "O18") (pin "2") (pinfunction "2_2") (pintype "passive"))
    )
    (net (code "23") (name "/IN20") (class "Default")
      (node (ref "I20") (pin "2") (pinfunction "2_2") (pintype "passive"))
      (node (ref "O19") (pin "2") (pinfunction "2_2") (pintype "passive"))
    )
    (net (code "24") (name "/IN21") (class "Default")
      (node (ref "I21") (pin "2") (pinfunction "2_2") (pintype "passive"))
      (node (ref "O20") (pin "2") (pinfunction "2_2") (pintype "passive"))
    )
    (net (code "25") (name "/IN22") (class "Default")
      (node (ref "I22") (pin "2") (pinfunction "2_2") (pintype "passive"))
      (node (ref "O21") (pin "2") (pinfunction "2_2") (pintype "passive"))
    )
    (net (code "26") (name "/IN23") (class "Default")
      (node (ref "I23") (pin "2") (pinfunction "2_2") (pintype "passive"))
      (node (ref "O22") (pin "2") (pinfunction "2_2") (pintype "passive"))
    )
    (net (code "27") (name "/IN24") (class "Default")
      (node (ref "I24") (pin "2") (pinfunction "2_2") (pintype "passive"))
      (node (ref "O23") (pin "2") (pinfunction "2_2") (pintype "passive"))
    )
    (net (code "28") (name "/IN25") (class "Default")
      (node (ref "I25") (pin "2") (pinfunction "2_2") (pintype "passive"))
      (node (ref "O24") (pin "2") (pinfunction "2_2") (pintype "passive"))
    )
    (net (code "29") (name "/IN26") (class "Default")
      (node (ref "I26") (pin "2") (pinfunction "2_2") (pintype "passive"))
      (node (ref "O25") (pin "2") (pinfunction "2_2") (pintype "passive"))
    )
    (net (code "30") (name "/IN27") (class "Default")
      (node (ref "I27") (pin "2") (pinfunction "2_2") (pintype "passive"))
      (node (ref "O26") (pin "2") (pinfunction "2_2") (pintype "passive"))
    )
    (net (code "31") (name "/IN28") (class "Default")
      (node (ref "I28") (pin "2") (pinfunction "2_2") (pintype "passive"))
      (node (ref "O27") (pin "2") (pinfunction "2_2") (pintype "passive"))
    )
    (net (code "32") (name "/IN29") (class "Default")
      (node (ref "I29") (pin "2") (pinfunction "2_2") (pintype "passive"))
      (node (ref "O28") (pin "2") (pinfunction "2_2") (pintype "passive"))
    )
    (net (code "33") (name "/IN30") (class "Default")
      (node (ref "I30") (pin "2") (pinfunction "2_2") (pintype "passive"))
      (node (ref "O29") (pin "2") (pinfunction "2_2") (pintype "passive"))
    )
    (net (code "34") (name "/IN31") (class "Default")
      (node (ref "I31") (pin "2") (pinfunction "2_2") (pintype "passive"))
      (node (ref "O30") (pin "2") (pinfunction "2_2") (pintype "passive"))
    )
    (net (code "35") (name "/IN32") (class "Default")
      (node (ref "I32") (pin "2") (pinfunction "2_2") (pintype "passive"))
      (node (ref "O31") (pin "2") (pinfunction "2_2") (pintype "passive"))
    )
    (net (code "36") (name "/IN33") (class "Default")
      (node (ref "I33") (pin "2") (pinfunction "2_2") (pintype "passive"))
      (node (ref "O32") (pin "2") (pinfunction "2_2") (pintype "passive"))
    )
    (net (code "37") (name "/IN34") (class "Default")
      (node (ref "I34") (pin "2") (pinfunction "2_2") (pintype "passive"))
      (node (ref "O33") (pin "2") (pinfunction "2_2") (pintype "passive"))
    )
    (net (code "38") (name "/IN35") (class "Default")
      (node (ref "I35") (pin "2") (pinfunction "2_2") (pintype "passive"))
      (node (ref "O34") (pin "2") (pinfunction "2_2") (pintype "passive"))
    )
    (net (code "39") (name "/IN36") (class "Default")
      (node (ref "I36") (pin "2") (pinfunction "2_2") (pintype "passive"))
      (node (ref "O35") (pin "2") (pinfunction "2_2") (pintype "passive"))
    )
    (net (code "40") (name "/IN37") (class "Default")
      (node (ref "I37") (pin "2") (pinfunction "2_2") (pintype "passive"))
      (node (ref "O36") (pin "2") (pinfunction "2_2") (pintype "passive"))
    )
    (net (code "41") (name "/IN38") (class "Default")
      (node (ref "I38") (pin "2") (pinfunction "2_2") (pintype "passive"))
      (node (ref "O37") (pin "2") (pinfunction "2_2") (pintype "passive"))
    )
    (net (code "42") (name "/IN39") (class "Default")
      (node (ref "I39") (pin "2") (pinfunction "2_2") (pintype "passive"))
      (node (ref "O38") (pin "2") (pinfunction "2_2") (pintype "passive"))
    )
    (net (code "43") (name "/IN40") (class "Default")
      (node (ref "I40") (pin "2") (pinfunction "2_2") (pintype "passive"))
      (node (ref "O39") (pin "2") (pinfunction "2_2") (pintype "passive"))
    )
    (net (code "44") (name "/IN41") (class "Default")
      (node (ref "I41") (pin "2") (pinfunction "2_2") (pintype "passive"))
      (node (ref "O40") (pin "2") (pinfunction "2_2") (pintype "passive"))
    )
    (net (code "45") (name "/IN42") (class "Default")
      (node (ref "I42") (pin "2") (pinfunction "2_2") (pintype "passive"))
      (node (ref "O41") (pin "2") (pinfunction "2_2") (pintype "passive"))
    )
    (net (code "46") (name "/IN43") (class "Default")
      (node (ref "I43") (pin "2") (pinfunction "2_2") (pintype "passive"))
      (node (ref "O42") (pin "2") (pinfunction "2_2") (pintype "passive"))
    )
    (net (code "47") (name "/IN44") (class "Default")
      (node (ref "I44") (pin "2") (pinfunction "2_2") (pintype "passive"))
      (node (ref "O43") (pin "2") (pinfunction "2_2") (pintype "passive"))
    )
    (net (code "48") (name "/IN45") (class "Default")
      (node (ref "I45") (pin "2") (pinfunction "2_2") (pintype "passive"))
      (node (ref "O44") (pin "2") (pinfunction "2_2") (pintype "passive"))
    )
    (net (code "49") (name "/IN46") (class "Default")
      (node (ref "I46") (pin "2") (pinfunction "2_2") (pintype "passive"))
      (node (ref "O45") (pin "2") (pinfunction "2_2") (pintype "passive"))
    )
    (net (code "50") (name "/IN47") (class "Default")
      (node (ref "I47") (pin "2") (pinfunction "2_2") (pintype "passive"))
      (node (ref "O46") (pin "2") (pinfunction "2_2") (pintype "passive"))
    )
    (net (code "51") (name "/IN48") (class "Default")
      (node (ref "I48") (pin "2") (pinfunction "2_2") (pintype "passive"))
      (node (ref "O47") (pin "2") (pinfunction "2_2") (pintype "passive"))
    )
    (net (code "52") (name "GND") (class "Default")
      (node (ref "I1") (pin "3") (pinfunction "3_3") (pintype "passive"))
      (node (ref "I10") (pin "3") (pinfunction "3_3") (pintype "passive"))
      (node (ref "I11") (pin "3") (pinfunction "3_3") (pintype "passive"))
      (node (ref "I12") (pin "3") (pinfunction "3_3") (pintype "passive"))
      (node (ref "I13") (pin "3") (pinfunction "3_3") (pintype "passive"))
      (node (ref "I14") (pin "3") (pinfunction "3_3") (pintype "passive"))
      (node (ref "I15") (pin "3") (pinfunction "3_3") (pintype "passive"))
      (node (ref "I16") (pin "3") (pinfunction "3_3") (pintype "passive"))
      (node (ref "I17") (pin "3") (pinfunction "3_3") (pintype "passive"))
      (node (ref "I18") (pin "3") (pinfunction "3_3") (pintype "passive"))
      (node (ref "I19") (pin "3") (pinfunction "3_3") (pintype "passive"))
      (node (ref "I2") (pin "3") (pinfunction "3_3") (pintype "passive"))
      (node (ref "I20") (pin "3") (pinfunction "3_3") (pintype "passive"))
      (node (ref "I21") (pin "3") (pinfunction "3_3") (pintype "passive"))
      (node (ref "I22") (pin "3") (pinfunction "3_3") (pintype "passive"))
      (node (ref "I23") (pin "3") (pinfunction "3_3") (pintype "passive"))
      (node (ref "I24") (pin "3") (pinfunction "3_3") (pintype "passive"))
      (node (ref "I25") (pin "3") (pinfunction "3_3") (pintype "passive"))
      (node (ref "I26") (pin "3") (pinfunction "3_3") (pintype "passive"))
      (node (ref "I27") (pin "3") (pinfunction "3_3") (pintype "passive"))
      (node (ref "I28") (pin "3") (pinfunction "3_3") (pintype "passive"))
      (node (ref "I29") (pin "3") (pinfunction "3_3") (pintype "passive"))
      (node (ref "I3") (pin "3") (pinfunction "3_3") (pintype "passive"))
      (node (ref "I30") (pin "3") (pinfunction "3_3") (pintype "passive"))
      (node (ref "I31") (pin "3") (pinfunction "3_3") (pintype "passive"))
      (node (ref "I32") (pin "3") (pinfunction "3_3") (pintype "passive"))
      (node (ref "I33") (pin "3") (pinfunction "3_3") (pintype "passive"))
      (node (ref "I34") (pin "3") (pinfunction "3_3") (pintype "passive"))
      (node (ref "I35") (pin "3") (pinfunction "3_3") (pintype "passive"))
      (node (ref "I36") (pin "3") (pinfunction "3_3") (pintype "passive"))
      (node (ref "I37") (pin "3") (pinfunction "3_3") (pintype "passive"))
      (node (ref "I38") (pin "3") (pinfunction "3_3") (pintype "passive"))
      (node (ref "I39") (pin "3") (pinfunction "3_3") (pintype "passive"))
      (node (ref "I4") (pin "3") (pinfunction "3_3") (pintype "passive"))
      (node (ref "I40") (pin "3") (pinfunction "3_3") (pintype "passive"))
      (node (ref "I41") (pin "3") (pinfunction "3_3") (pintype "passive"))
      (node (ref "I42") (pin "3") (pinfunction "3_3") (pintype "passive"))
      (node (ref "I43") (pin "3") (pinfunction "3_3") (pintype "passive"))
      (node (ref "I44") (pin "3") (pinfunction "3_3") (pintype "passive"))
      (node (ref "I45") (pin "3") (pinfunction "3_3") (pintype "passive"))
      (node (ref "I46") (pin "3") (pinfunction "3_3") (pintype "passive"))
      (node (ref "I47") (pin "3") (pinfunction "3_3") (pintype "passive"))
      (node (ref "I48") (pin "3") (pinfunction "3_3") (pintype "passive"))
      (node (ref "I5") (pin "3") (pinfunction "3_3") (pintype "passive"))
      (node (ref "I6") (pin "3") (pinfunction "3_3") (pintype "passive"))
      (node (ref "I7") (pin "3") (pinfunction "3_3") (pintype "passive"))
      (node (ref "I8") (pin "3") (pinfunction "3_3") (pintype "passive"))
      (node (ref "I9") (pin "3") (pinfunction "3_3") (pintype "passive"))
      (node (ref "JP1") (pin "14") (pinfunction "14_14") (pintype "passive"))
      (node (ref "JP11") (pin "14") (pinfunction "14_14") (pintype "passive"))
      (node (ref "JP2") (pin "14") (pinfunction "14_14") (pintype "passive"))
      (node (ref "JP21") (pin "14") (pinfunction "14_14") (pintype "passive"))
      (node (ref "JP4") (pin "1") (pinfunction "1_1") (pintype "passive"))
      (node (ref "O1") (pin "1") (pinfunction "1_1") (pintype "passive"))
      (node (ref "O10") (pin "1") (pinfunction "1_1") (pintype "passive"))
      (node (ref "O11") (pin "1") (pinfunction "1_1") (pintype "passive"))
      (node (ref "O12") (pin "1") (pinfunction "1_1") (pintype "passive"))
      (node (ref "O13") (pin "1") (pinfunction "1_1") (pintype "passive"))
      (node (ref "O14") (pin "1") (pinfunction "1_1") (pintype "passive"))
      (node (ref "O15") (pin "1") (pinfunction "1_1") (pintype "passive"))
      (node (ref "O16") (pin "1") (pinfunction "1_1") (pintype "passive"))
      (node (ref "O17") (pin "1") (pinfunction "1_1") (pintype "passive"))
      (node (ref "O18") (pin "1") (pinfunction "1_1") (pintype "passive"))
      (node (ref "O19") (pin "1") (pinfunction "1_1") (pintype "passive"))
      (node (ref "O2") (pin "1") (pinfunction "1_1") (pintype "passive"))
      (node (ref "O20") (pin "1") (pinfunction "1_1") (pintype "passive"))
      (node (ref "O21") (pin "1") (pinfunction "1_1") (pintype "passive"))
      (node (ref "O22") (pin "1") (pinfunction "1_1") (pintype "passive"))
      (node (ref "O23") (pin "1") (pinfunction "1_1") (pintype "passive"))
      (node (ref "O24") (pin "1") (pinfunction "1_1") (pintype "passive"))
      (node (ref "O25") (pin "1") (pinfunction "1_1") (pintype "passive"))
      (node (ref "O26") (pin "1") (pinfunction "1_1") (pintype "passive"))
      (node (ref "O27") (pin "1") (pinfunction "1_1") (pintype "passive"))
      (node (ref "O28") (pin "1") (pinfunction "1_1") (pintype "passive"))
      (node (ref "O29") (pin "1") (pinfunction "1_1") (pintype "passive"))
      (node (ref "O3") (pin "1") (pinfunction "1_1") (pintype "passive"))
      (node (ref "O30") (pin "1") (pinfunction "1_1") (pintype "passive"))
      (node (ref "O31") (pin "1") (pinfunction "1_1") (pintype "passive"))
      (node (ref "O32") (pin "1") (pinfunction "1_1") (pintype "passive"))
      (node (ref "O33") (pin "1") (pinfunction "1_1") (pintype "passive"))
      (node (ref "O34") (pin "1") (pinfunction "1_1") (pintype "passive"))
      (node (ref "O35") (pin "1") (pinfunction "1_1") (pintype "passive"))
      (node (ref "O36") (pin "1") (pinfunction "1_1") (pintype "passive"))
      (node (ref "O37") (pin "1") (pinfunction "1_1") (pintype "passive"))
      (node (ref "O38") (pin "1") (pinfunction "1_1") (pintype "passive"))
      (node (ref "O39") (pin "1") (pinfunction "1_1") (pintype "passive"))
      (node (ref "O4") (pin "1") (pinfunction "1_1") (pintype "passive"))
      (node (ref "O40") (pin "1") (pinfunction "1_1") (pintype "passive"))
      (node (ref "O41") (pin "1") (pinfunction "1_1") (pintype "passive"))
      (node (ref "O42") (pin "1") (pinfunction "1_1") (pintype "passive"))
      (node (ref "O43") (pin "1") (pinfunction "1_1") (pintype "passive"))
      (node (ref "O44") (pin "1") (pinfunction "1_1") (pintype "passive"))
      (node (ref "O45") (pin "1") (pinfunction "1_1") (pintype "passive"))
      (node (ref "O46") (pin "1") (pinfunction "1_1") (pintype "passive"))
      (node (ref "O47") (pin "1") (pinfunction "1_1") (pintype "passive"))
      (node (ref "O48") (pin "1") (pinfunction "1_1") (pintype "passive"))
      (node (ref "O5") (pin "1") (pinfunction "1_1") (pintype "passive"))
      (node (ref "O6") (pin "1") (pinfunction "1_1") (pintype "passive"))
      (node (ref "O7") (pin "1") (pinfunction "1_1") (pintype "passive"))
      (node (ref "O8") (pin "1") (pinfunction "1_1") (pintype "passive"))
      (node (ref "O9") (pin "1") (pinfunction "1_1") (pintype "passive"))
    )
    (net (code "53") (name "Net-(JP1-Pad1)") (class "Default")
      (node (ref "JP1") (pin "1") (pinfunction "1_1") (pintype "passive"))
      (node (ref "JP11") (pin "1") (pinfunction "1_1") (pintype "passive"))
    )
    (net (code "54") (name "Net-(JP1-Pad2)") (class "Default")
      (node (ref "JP1") (pin "2") (pinfunction "2_2") (pintype "passive"))
      (node (ref "JP11") (pin "2") (pinfunction "2_2") (pintype "passive"))
    )
    (net (code "55") (name "Net-(JP1-Pad3)") (class "Default")
      (node (ref "JP1") (pin "3") (pinfunction "3_3") (pintype "passive"))
      (node (ref "JP11") (pin "3") (pinfunction "3_3") (pintype "passive"))
    )
    (net (code "56") (name "Net-(JP1-Pad4)") (class "Default")
      (node (ref "JP1") (pin "4") (pinfunction "4_4") (pintype "passive"))
      (node (ref "JP11") (pin "4") (pinfunction "4_4") (pintype "passive"))
    )
    (net (code "57") (name "Net-(JP1-Pad5)") (class "Default")
      (node (ref "JP1") (pin "5") (pinfunction "5_5") (pintype "passive"))
      (node (ref "JP11") (pin "5") (pinfunction "5_5") (pintype "passive"))
    )
    (net (code "58") (name "Net-(JP1-Pad6)") (class "Default")
      (node (ref "JP1") (pin "6") (pinfunction "6_6") (pintype "passive"))
      (node (ref "JP11") (pin "6") (pinfunction "6_6") (pintype "passive"))
    )
    (net (code "59") (name "Net-(JP1-Pad7)") (class "Default")
      (node (ref "JP1") (pin "7") (pinfunction "7_7") (pintype "passive"))
      (node (ref "JP11") (pin "7") (pinfunction "7_7") (pintype "passive"))
    )
    (net (code "60") (name "Net-(JP1-Pad8)") (class "Default")
      (node (ref "JP1") (pin "8") (pinfunction "8_8") (pintype "passive"))
      (node (ref "JP11") (pin "8") (pinfunction "8_8") (pintype "passive"))
    )
    (net (code "61") (name "Net-(JP1-Pad9)") (class "Default")
      (node (ref "JP1") (pin "9") (pinfunction "9_9") (pintype "passive"))
      (node (ref "JP11") (pin "9") (pinfunction "9_9") (pintype "passive"))
    )
    (net (code "62") (name "Net-(JP1-Pad10)") (class "Default")
      (node (ref "JP1") (pin "10") (pinfunction "10_10") (pintype "passive"))
      (node (ref "JP11") (pin "10") (pinfunction "10_10") (pintype "passive"))
    )
    (net (code "63") (name "Net-(JP1-Pad12)") (class "Default")
      (node (ref "JP1") (pin "12") (pinfunction "12_12") (pintype "passive"))
      (node (ref "JP11") (pin "12") (pinfunction "12_12") (pintype "passive"))
    )
    (net (code "64") (name "Net-(JP1-Pad13)") (class "Default")
      (node (ref "JP1") (pin "13") (pinfunction "13_13") (pintype "passive"))
      (node (ref "JP11") (pin "13") (pinfunction "13_13") (pintype "passive"))
    )
    (net (code "65") (name "Net-(JP2-Pad1)") (class "Default")
      (node (ref "JP2") (pin "1") (pinfunction "1_1") (pintype "passive"))
      (node (ref "JP21") (pin "1") (pinfunction "1_1") (pintype "passive"))
    )
    (net (code "66") (name "Net-(JP2-Pad2)") (class "Default")
      (node (ref "JP2") (pin "2") (pinfunction "2_2") (pintype "passive"))
      (node (ref "JP21") (pin "2") (pinfunction "2_2") (pintype "passive"))
    )
    (net (code "67") (name "Net-(JP2-Pad3)") (class "Default")
      (node (ref "JP2") (pin "3") (pinfunction "3_3") (pintype "passive"))
      (node (ref "JP21") (pin "3") (pinfunction "3_3") (pintype "passive"))
    )
    (net (code "68") (name "Net-(JP2-Pad4)") (class "Default")
      (node (ref "JP2") (pin "4") (pinfunction "4_4") (pintype "passive"))
      (node (ref "JP21") (pin "4") (pinfunction "4_4") (pintype "passive"))
    )
    (net (code "69") (name "Net-(JP2-Pad5)") (class "Default")
      (node (ref "JP2") (pin "5") (pinfunction "5_5") (pintype "passive"))
      (node (ref "JP21") (pin "5") (pinfunction "5_5") (pintype "passive"))
    )
    (net (code "70") (name "Net-(JP2-Pad6)") (class "Default")
      (node (ref "JP2") (pin "6") (pinfunction "6_6") (pintype "passive"))
      (node (ref "JP21") (pin "6") (pinfunction "6_6") (pintype "passive"))
    )
    (net (code "71") (name "Net-(JP2-Pad7)") (class "Default")
      (node (ref "JP2") (pin "7") (pinfunction "7_7") (pintype "passive"))
      (node (ref "JP21") (pin "7") (pinfunction "7_7") (pintype "passive"))
    )
    (net (code "72") (name "Net-(JP2-Pad8)") (class "Default")
      (node (ref "JP2") (pin "8") (pinfunction "8_8") (pintype "passive"))
      (node (ref "JP21") (pin "8") (pinfunction "8_8") (pintype "passive"))
    )
    (net (code "73") (name "Net-(JP2-Pad9)") (class "Default")
      (node (ref "JP2") (pin "9") (pinfunction "9_9") (pintype "passive"))
      (node (ref "JP21") (pin "9") (pinfunction "9_9") (pintype "passive"))
    )
    (net (code "74") (name "Net-(JP2-Pad10)") (class "Default")
      (node (ref "JP2") (pin "10") (pinfunction "10_10") (pintype "passive"))
      (node (ref "JP21") (pin "10") (pinfunction "10_10") (pintype "passive"))
    )
    (net (code "75") (name "Net-(JP2-Pad11)") (class "Default")
      (node (ref "JP2") (pin "11") (pinfunction "11_11") (pintype "passive"))
      (node (ref "JP21") (pin "11") (pinfunction "11_11") (pintype "passive"))
    )
    (net (code "76") (name "Net-(JP2-Pad12)") (class "Default")
      (node (ref "JP2") (pin "12") (pinfunction "12_12") (pintype "passive"))
      (node (ref "JP21") (pin "12") (pinfunction "12_12") (pintype "passive"))
    )
    (net (code "77") (name "Net-(JP2-Pad13)") (class "Default")
      (node (ref "JP2") (pin "13") (pinfunction "13_13") (pintype "passive"))
      (node (ref "JP21") (pin "13") (pinfunction "13_13") (pintype "passive"))
    )
    (net (code "78") (name "Net-(JP2-Pad15)") (class "Default")
      (node (ref "JP2") (pin "15") (pinfunction "15_15") (pintype "passive"))
      (node (ref "JP21") (pin "15") (pinfunction "15_15") (pintype "passive"))
    )
    (net (code "79") (name "Net-(JP3-Pad2)") (class "Default")
      (node (ref "JP3") (pin "2") (pinfunction "2_2") (pintype "passive"))
      (node (ref "JP5") (pin "1") (pinfunction "1_1") (pintype "passive"))
      (node (ref "JP6") (pin "2") (pinfunction "2_2") (pintype "passive"))
    )
    (net (code "80") (name "unconnected-(O48-Pad2)") (class "Default")
      (node (ref "O48") (pin "2") (pinfunction "2_2") (pintype "passive"))
    )
  )
)
